# bat_ctl.net
KiCad netlist of a schematic drawn in Altium Designer
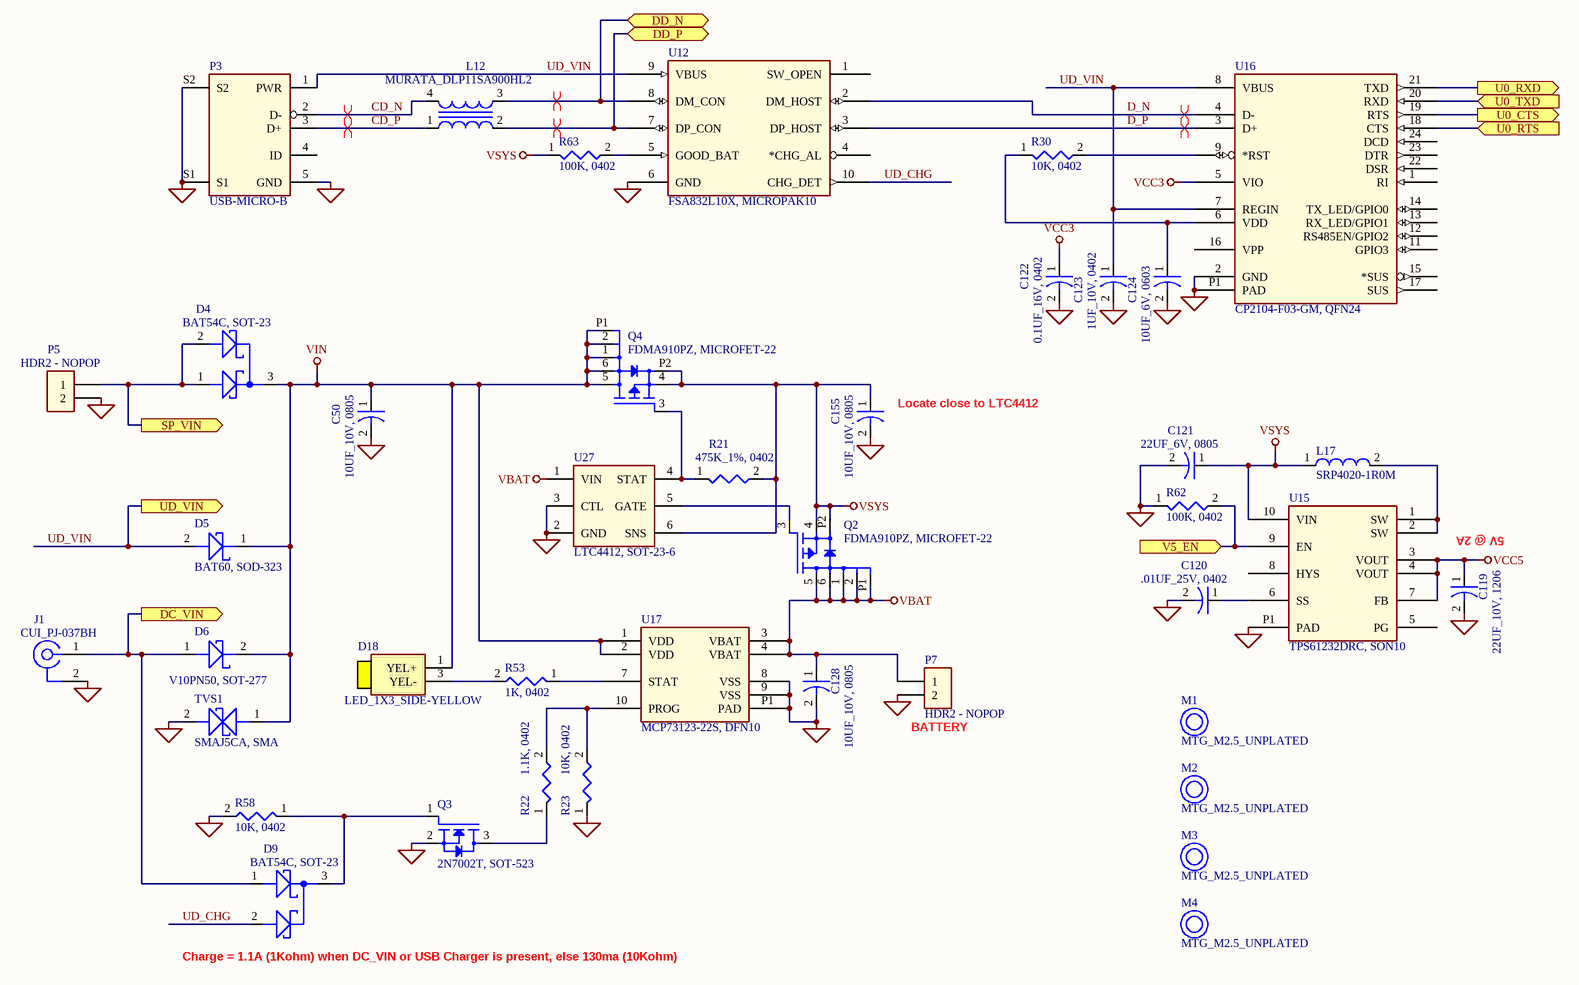
[diagram p0: bat_ctl.SchDoc]

(export (version "E")
  (design (tool "Eeschema 10.0.6"))
  (components
    (comp (ref "C50")
      (value "10UF_10V, 0805")
      (footprint "0805C")
      (description "CAP - 0805 PKG")
      (libsource (lib "COGENT_Library") (part "10UF_10V, 0805"))
    )
    (comp (ref "C119")
      (value "22UF_10V, 1206")
      (footprint "1206C")
      (description "CAP - 1206 PKG")
      (libsource (lib "COGENT_Library") (part "22UF_10V, 1206"))
    )
    (comp (ref "C120")
      (value ".01UF_25V, 0402")
      (footprint "0402C")
      (description "CAP - 0402 PKG")
      (libsource (lib "COGENT_Library") (part ".01UF_25V, 0402"))
    )
    (comp (ref "C121")
      (value "22UF_6V, 0805")
      (footprint "0805C")
      (description "CAP - 0805 PKG")
      (libsource (lib "COGENT_Library") (part "22UF_6V, 0805"))
    )
    (comp (ref "C122")
      (value "0.1UF_16V, 0402")
      (footprint "0402C")
      (description "CAP - 0402 PKG")
      (libsource (lib "COGENT_Library") (part "0.1UF_16V, 0402"))
    )
    (comp (ref "C123")
      (value "1UF_10V, 0402")
      (footprint "0402C")
      (description "CAP - 0402 PKG")
      (libsource (lib "COGENT_Library") (part "1UF_10V, 0402"))
    )
    (comp (ref "C124")
      (value "10UF_6V, 0603")
      (footprint "0603C")
      (description "CAP - 0603 PKG")
      (libsource (lib "COGENT_Library") (part "10UF_6V, 0603"))
    )
    (comp (ref "C128")
      (value "10UF_10V, 0805")
      (footprint "0805C")
      (description "CAP - 0805 PKG")
      (libsource (lib "COGENT_Library") (part "10UF_10V, 0805"))
    )
    (comp (ref "C155")
      (value "10UF_10V, 0805")
      (footprint "0805C")
      (description "CAP - 0805 PKG")
      (libsource (lib "COGENT_Library") (part "10UF_10V, 0805"))
    )
    (comp (ref "D4")
      (value "BAT54C, SOT-23")
      (footprint "SOT-23")
      (description "DIODE - DUAL SCHOTTKY, COMMON CATHODE, 30V, 200MA")
      (libsource (lib "COGENT_Library") (part "BAT54C, SOT-23"))
    )
    (comp (ref "D5")
      (value "BAT60, SOD-323")
      (footprint "SOD-323")
      (description "DIODE - POWER, SCHOTTKY, 10V, 3A")
      (libsource (lib "COGENT_Library") (part "BAT60, SOD-323"))
    )
    (comp (ref "D6")
      (value "V10PN50, SOT-277")
      (footprint "SOT-277")
      (description "DIODE - SCHOTTKY, 50V, 10A")
      (libsource (lib "COGENT_Library") (part "V10PN50, SOT-277"))
    )
    (comp (ref "D9")
      (value "BAT54C, SOT-23")
      (footprint "SOT-23")
      (description "DIODE - DUAL SCHOTTKY, COMMON CATHODE, 30V, 200MA")
      (libsource (lib "COGENT_Library") (part "BAT54C, SOT-23"))
    )
    (comp (ref "D18")
      (value "LED_1X3_SIDE-YELLOW")
      (footprint "LED_1X3_SIDE-YELLOW")
      (description "LED - SIDEVIEW, SMT, YELLOW")
      (libsource (lib "COGENT_Library") (part "LED_1X3_SIDE-YELLOW"))
    )
    (comp (ref "J1")
      (value "CUI_PJ-037BH")
      (footprint "CUI_PJ-037B")
      (description "CONN - DC JACK, 2.5mm CENTER PLUS, 5 AMP")
      (libsource (lib "COGENT_Library") (part "CUI_PJ-037BH"))
    )
    (comp (ref "L12")
      (value "MURATA_DLP11SA900HL2")
      (footprint "PANASONIC_EXC24C")
      (description "FERRITE - COMMON MODE FILTER, USB2/HDMI/GIGe, FILM")
      (libsource (lib "COGENT_Library") (part "MURATA_DLP11SA900HL2"))
    )
    (comp (ref "L17")
      (value "SRP4020-1R0M")
      (footprint "SRP4020")
      (description "INDUCTOR - 1.0UH, 5/6A, 4MM x 4MM x 2MM, 22mohm")
      (libsource (lib "COGENT_Library") (part "SRP4020-1R0M"))
    )
    (comp (ref "M1")
      (value "MTG_M2.5_UNPLATED")
      (footprint "MTG_M2.5_UNPLATED")
      (description "MTG HOLE - 2.75mm HOLE 2-56 OR M2.5")
      (libsource (lib "COGENT_Library") (part "MTG_M2.5_UNPLATED"))
    )
    (comp (ref "M2")
      (value "MTG_M2.5_UNPLATED")
      (footprint "MTG_M2.5_UNPLATED")
      (description "MTG HOLE - 2.75mm HOLE 2-56 OR M2.5")
      (libsource (lib "COGENT_Library") (part "MTG_M2.5_UNPLATED"))
    )
    (comp (ref "M3")
      (value "MTG_M2.5_UNPLATED")
      (footprint "MTG_M2.5_UNPLATED")
      (description "MTG HOLE - 2.75mm HOLE 2-56 OR M2.5")
      (libsource (lib "COGENT_Library") (part "MTG_M2.5_UNPLATED"))
    )
    (comp (ref "M4")
      (value "MTG_M2.5_UNPLATED")
      (footprint "MTG_M2.5_UNPLATED")
      (description "MTG HOLE - 2.75mm HOLE 2-56 OR M2.5")
      (libsource (lib "COGENT_Library") (part "MTG_M2.5_UNPLATED"))
    )
    (comp (ref "P3")
      (value "USB-MICRO-B")
      (footprint "USB-MICRO-B")
      (description "CONN - USB TYPE B MICRO")
      (libsource (lib "COGENT_Library") (part "USB-MICRO-B"))
    )
    (comp (ref "P5")
      (value "HDR2 - NOPOP")
      (footprint "HDR2X1-NOPOP")
      (description "HEADER - 2-PIN, HOLES ONLY FOR WIRE")
      (libsource (lib "") (part "HDR2 - NOPOP_1"))
    )
    (comp (ref "P7")
      (value "HDR2 - NOPOP")
      (footprint "HDR2X1-NOPOP")
      (description "HEADER - 2-PIN, HOLES ONLY FOR WIRE")
      (libsource (lib "COGENT_Library") (part "HDR2 - NOPOP"))
    )
    (comp (ref "Q2")
      (value "FDMA910PZ, MICROFET-22")
      (footprint "MICROFET-22")
      (description "P-FET - 20V, 7.2A @ 1.8Vgs, 34mohm")
      (libsource (lib "COGENT_Library") (part "FDMA910PZ, MICROFET-22"))
    )
    (comp (ref "Q3")
      (value "2N7002T, SOT-523")
      (footprint "SOT-523")
      (description "N-FET - 60V, 500ma @ 10V, Vgs(th) 2V")
      (libsource (lib "COGENT_Library") (part "2N7002T, SOT-523"))
    )
    (comp (ref "Q4")
      (value "FDMA910PZ, MICROFET-22")
      (footprint "MICROFET-22")
      (description "P-FET - 20V, 7.2A @ 1.8Vgs, 34mohm")
      (libsource (lib "COGENT_Library") (part "FDMA910PZ, MICROFET-22"))
    )
    (comp (ref "R21")
      (value "475K_1%, 0402")
      (footprint "0402R")
      (description "RES - 0402 PKG")
      (libsource (lib "COGENT_Library") (part "475K_1%, 0402"))
    )
    (comp (ref "R22")
      (value "1.1K, 0402")
      (footprint "0402R")
      (description "RES - 0402 PKG")
      (libsource (lib "COGENT_Library") (part "1.1K, 0402"))
    )
    (comp (ref "R23")
      (value "10K, 0402")
      (footprint "0402R")
      (description "RES - 0402 PKG")
      (libsource (lib "COGENT_Library") (part "10K, 0402"))
    )
    (comp (ref "R30")
      (value "10K, 0402")
      (footprint "0402R")
      (description "RES - 0402 PKG")
      (libsource (lib "COGENT_Library") (part "10K, 0402"))
    )
    (comp (ref "R53")
      (value "1K, 0402")
      (footprint "0402R")
      (description "RES - 0402 PKG")
      (libsource (lib "COGENT_Library") (part "1K, 0402"))
    )
    (comp (ref "R58")
      (value "10K, 0402")
      (footprint "0402R")
      (description "RES - 0402 PKG")
      (libsource (lib "COGENT_Library") (part "10K, 0402"))
    )
    (comp (ref "R62")
      (value "100K, 0402")
      (footprint "0402R")
      (description "RES - 0402 PKG")
      (libsource (lib "COGENT_Library") (part "100K, 0402"))
    )
    (comp (ref "R63")
      (value "100K, 0402")
      (footprint "0402R")
      (description "RES - 0402 PKG")
      (libsource (lib "COGENT_Library") (part "100K, 0402"))
    )
    (comp (ref "TVS1")
      (value "SMAJ5CA, SMA")
      (footprint "SMA")
      (description "DIODE - TVS, 6.4V MIN., 7.25V MAX.")
      (libsource (lib "COGENT_Library") (part "SMAJ5CA, SMA"))
    )
    (comp (ref "U12")
      (value "FSA832L10X, MICROPAK10")
      (footprint "MICROpack10")
      (description "USB - BATTERY CHARGER DETECTION W/SWITCH")
      (libsource (lib "COGENT_Library") (part "FSA832L10X, MICROPAK10"))
    )
    (comp (ref "U15")
      (value "TPS61232DRC, SON10")
      (footprint "SON10")
      (description "SWITCHER - 500ua Iq, BOOST 5A, 2.3V TO 5.5V IN, 2.5V TO 5.5V OUT")
      (libsource (lib "COGENT_Library") (part "TPS61232DRC, SON10"))
    )
    (comp (ref "U16")
      (value "CP2104-F03-GM, QFN24")
      (footprint "QFN24")
      (description "USB - UART W/4 GPIO")
      (libsource (lib "COGENT_Library") (part "CP2104-F03-GM, QFN24"))
    )
    (comp (ref "U17")
      (value "MCP73123-22S, DFN10")
      (footprint "DFN10")
      (description "IC - BATTERY CHARGER, 1 CELL LiFePO4, 1.1 AMAX")
      (libsource (lib "COGENT_Library") (part "MCP73123-22S, DFN10"))
    )
    (comp (ref "U27")
      (value "LTC4412, SOT-23-6")
      (footprint "SOT-23-6")
      (description "IC - POWER SOURCE SELECTOR")
      (libsource (lib "COGENT_Library") (part "LTC4412, SOT-23-6"))
    )
  )
  (nets
    (net (code "1") (name "/CD_N") (class "Default")
      (node (ref "L12") (pin "4") (pinfunction "4_4") (pintype "passive"))
      (node (ref "P3") (pin "2") (pinfunction "D-_2") (pintype "passive"))
    )
    (net (code "2") (name "/CD_P") (class "Default")
      (node (ref "L12") (pin "1") (pinfunction "1_1") (pintype "passive"))
      (node (ref "P3") (pin "3") (pinfunction "D+_3") (pintype "passive"))
    )
    (net (code "3") (name "/DC_VIN") (class "Default")
      (node (ref "D6") (pin "1") (pinfunction "ANODE_1") (pintype "passive"))
      (node (ref "D9") (pin "1") (pinfunction "1_1") (pintype "passive"))
      (node (ref "J1") (pin "1") (pinfunction "1_1") (pintype "passive"))
    )
    (net (code "4") (name "/DD_N") (class "Default")
      (node (ref "L12") (pin "3") (pinfunction "3_3") (pintype "passive"))
      (node (ref "U12") (pin "8") (pinfunction "DM_CON_8") (pintype "bidirectional"))
    )
    (net (code "5") (name "/DD_P") (class "Default")
      (node (ref "L12") (pin "2") (pinfunction "2_2") (pintype "passive"))
      (node (ref "U12") (pin "7") (pinfunction "DP_CON_7") (pintype "bidirectional"))
    )
    (net (code "6") (name "/D_N") (class "Default")
      (node (ref "U12") (pin "2") (pinfunction "DM_HOST_2") (pintype "bidirectional"))
      (node (ref "U16") (pin "4") (pinfunction "D-_4") (pintype "passive"))
    )
    (net (code "7") (name "/D_P") (class "Default")
      (node (ref "U12") (pin "3") (pinfunction "DP_HOST_3") (pintype "bidirectional"))
      (node (ref "U16") (pin "3") (pinfunction "D+_3") (pintype "passive"))
    )
    (net (code "8") (name "/SP_VIN") (class "Default")
      (node (ref "D4") (pin "1") (pinfunction "1_1") (pintype "passive"))
      (node (ref "D4") (pin "2") (pinfunction "2_2") (pintype "passive"))
      (node (ref "P5") (pin "1") (pinfunction "1_1") (pintype "passive"))
    )
    (net (code "9") (name "/U0_CTS") (class "Default")
      (node (ref "U16") (pin "19") (pinfunction "RTS_19") (pintype "output"))
    )
    (net (code "10") (name "/U0_RTS") (class "Default")
      (node (ref "U16") (pin "18") (pinfunction "CTS_18") (pintype "input"))
    )
    (net (code "11") (name "/U0_RXD") (class "Default")
      (node (ref "U16") (pin "21") (pinfunction "TXD_21") (pintype "output"))
    )
    (net (code "12") (name "/U0_TXD") (class "Default")
      (node (ref "U16") (pin "20") (pinfunction "RXD_20") (pintype "input"))
    )
    (net (code "13") (name "/UD_CHG") (class "Default")
      (node (ref "D9") (pin "2") (pinfunction "2_2") (pintype "passive"))
      (node (ref "U12") (pin "10") (pinfunction "CHG_DET_10") (pintype "output"))
    )
    (net (code "14") (name "/UD_VIN") (class "Default")
      (node (ref "C123") (pin "1") (pinfunction "1_1") (pintype "passive"))
      (node (ref "D5") (pin "2") (pinfunction "ANODE_2") (pintype "passive"))
      (node (ref "P3") (pin "1") (pinfunction "PWR_1") (pintype "passive"))
      (node (ref "U12") (pin "9") (pinfunction "VBUS_9") (pintype "input"))
      (node (ref "U16") (pin "7") (pinfunction "REGIN_7") (pintype "power_in"))
      (node (ref "U16") (pin "8") (pinfunction "VBUS_8") (pintype "passive"))
    )
    (net (code "15") (name "/V5_EN") (class "Default")
      (node (ref "R62") (pin "2") (pinfunction "2_2") (pintype "passive"))
      (node (ref "U15") (pin "9") (pinfunction "EN_9") (pintype "passive"))
    )
    (net (code "16") (name "GND") (class "Default")
      (node (ref "C119") (pin "2") (pinfunction "2_2") (pintype "passive"))
      (node (ref "C120") (pin "2") (pinfunction "2_2") (pintype "passive"))
      (node (ref "C121") (pin "2") (pinfunction "2_2") (pintype "passive"))
      (node (ref "C122") (pin "2") (pinfunction "2_2") (pintype "passive"))
      (node (ref "C123") (pin "2") (pinfunction "2_2") (pintype "passive"))
      (node (ref "C124") (pin "2") (pinfunction "2_2") (pintype "passive"))
      (node (ref "C128") (pin "2") (pinfunction "2_2") (pintype "passive"))
      (node (ref "C155") (pin "2") (pinfunction "2_2") (pintype "passive"))
      (node (ref "C50") (pin "2") (pinfunction "2_2") (pintype "passive"))
      (node (ref "J1") (pin "2") (pinfunction "2_2") (pintype "passive"))
      (node (ref "P3") (pin "5") (pinfunction "GND_5") (pintype "passive"))
      (node (ref "P3") (pin "S1") (pinfunction "S1_S1") (pintype "passive"))
      (node (ref "P3") (pin "S2") (pinfunction "S2_S2") (pintype "passive"))
      (node (ref "P5") (pin "2") (pinfunction "2_2") (pintype "passive"))
      (node (ref "P7") (pin "2") (pinfunction "2_2") (pintype "passive"))
      (node (ref "Q3") (pin "2") (pinfunction "SOURCE_2") (pintype "passive"))
      (node (ref "R23") (pin "1") (pinfunction "1_1") (pintype "passive"))
      (node (ref "R58") (pin "2") (pinfunction "2_2") (pintype "passive"))
      (node (ref "R62") (pin "1") (pinfunction "1_1") (pintype "passive"))
      (node (ref "TVS1") (pin "2") (pinfunction "2_2") (pintype "passive"))
      (node (ref "U12") (pin "6") (pinfunction "GND_6") (pintype "power_in"))
      (node (ref "U15") (pin "P1") (pinfunction "PAD_P1") (pintype "power_in"))
      (node (ref "U16") (pin "2") (pinfunction "GND_2") (pintype "power_in"))
      (node (ref "U16") (pin "P1") (pinfunction "PAD_P1") (pintype "passive"))
      (node (ref "U17") (pin "8") (pinfunction "VSS_8") (pintype "passive"))
      (node (ref "U17") (pin "9") (pinfunction "VSS_9") (pintype "passive"))
      (node (ref "U17") (pin "P1") (pinfunction "PAD_P1") (pintype "passive"))
      (node (ref "U27") (pin "2") (pinfunction "GND_2") (pintype "passive"))
      (node (ref "U27") (pin "3") (pinfunction "CTL_3") (pintype "passive"))
    )
    (net (code "17") (name "Net-(D18-YEL-)") (class "Default")
      (node (ref "D18") (pin "3") (pinfunction "YEL-_3") (pintype "passive"))
      (node (ref "R53") (pin "2") (pinfunction "2_2") (pintype "passive"))
    )
    (net (code "18") (name "Net-(L17-Pad2)") (class "Default")
      (node (ref "L17") (pin "2") (pinfunction "2_2") (pintype "passive"))
      (node (ref "U15") (pin "1") (pinfunction "SW_1") (pintype "open_collector"))
      (node (ref "U15") (pin "2") (pinfunction "SW_2") (pintype "passive"))
    )
    (net (code "19") (name "Net-(Q3-DRAIN)") (class "Default")
      (node (ref "Q3") (pin "3") (pinfunction "DRAIN_3") (pintype "passive"))
      (node (ref "R22") (pin "1") (pinfunction "1_1") (pintype "passive"))
    )
    (net (code "20") (name "Net-(Q3-GATE)") (class "Default")
      (node (ref "D9") (pin "3") (pinfunction "3_3") (pintype "passive"))
      (node (ref "Q3") (pin "1") (pinfunction "GATE_1") (pintype "passive"))
      (node (ref "R58") (pin "1") (pinfunction "1_1") (pintype "passive"))
    )
    (net (code "21") (name "Net-(U12-GOOD_BAT)") (class "Default")
      (node (ref "R63") (pin "2") (pinfunction "2_2") (pintype "passive"))
      (node (ref "U12") (pin "5") (pinfunction "GOOD_BAT_5") (pintype "input"))
    )
    (net (code "22") (name "Net-(U15-SS)") (class "Default")
      (node (ref "C120") (pin "1") (pinfunction "1_1") (pintype "passive"))
      (node (ref "U15") (pin "6") (pinfunction "SS_6") (pintype "passive"))
    )
    (net (code "23") (name "Net-(U16-*RST)") (class "Default")
      (node (ref "R30") (pin "2") (pinfunction "2_2") (pintype "passive"))
      (node (ref "U16") (pin "9") (pinfunction "*RST_9") (pintype "bidirectional"))
    )
    (net (code "24") (name "Net-(U16-VDD)") (class "Default")
      (node (ref "C124") (pin "1") (pinfunction "1_1") (pintype "passive"))
      (node (ref "R30") (pin "1") (pinfunction "1_1") (pintype "passive"))
      (node (ref "U16") (pin "6") (pinfunction "VDD_6") (pintype "power_in"))
    )
    (net (code "25") (name "Net-(U17-PROG)") (class "Default")
      (node (ref "R22") (pin "2") (pinfunction "2_2") (pintype "passive"))
      (node (ref "R23") (pin "2") (pinfunction "2_2") (pintype "passive"))
      (node (ref "U17") (pin "10") (pinfunction "PROG_10") (pintype "passive"))
    )
    (net (code "26") (name "Net-(U17-STAT)") (class "Default")
      (node (ref "R53") (pin "1") (pinfunction "1_1") (pintype "passive"))
      (node (ref "U17") (pin "7") (pinfunction "STAT_7") (pintype "open_collector"))
    )
    (net (code "27") (name "Net-(U27-GATE)") (class "Default")
      (node (ref "Q2") (pin "3") (pinfunction "3_3") (pintype "passive"))
      (node (ref "U27") (pin "5") (pinfunction "GATE_5") (pintype "passive"))
    )
    (net (code "28") (name "Net-(U27-STAT)") (class "Default")
      (node (ref "Q4") (pin "3") (pinfunction "3_3") (pintype "passive"))
      (node (ref "R21") (pin "1") (pinfunction "1_1") (pintype "passive"))
      (node (ref "U27") (pin "4") (pinfunction "STAT_4") (pintype "passive"))
    )
    (net (code "29") (name "VBAT") (class "Default")
      (node (ref "C128") (pin "1") (pinfunction "1_1") (pintype "passive"))
      (node (ref "P7") (pin "1") (pinfunction "1_1") (pintype "passive"))
      (node (ref "Q2") (pin "1") (pinfunction "1_1") (pintype "passive"))
      (node (ref "Q2") (pin "2") (pinfunction "2_2") (pintype "passive"))
      (node (ref "Q2") (pin "5") (pinfunction "D1_5") (pintype "passive"))
      (node (ref "Q2") (pin "6") (pinfunction "D2_6") (pintype "passive"))
      (node (ref "Q2") (pin "P1") (pinfunction "D5_P1") (pintype "passive"))
      (node (ref "U17") (pin "3") (pinfunction "VBAT_3") (pintype "passive"))
      (node (ref "U17") (pin "4") (pinfunction "VBAT_4") (pintype "passive"))
      (node (ref "U27") (pin "1") (pinfunction "VIN_1") (pintype "passive"))
    )
    (net (code "30") (name "VCC3") (class "Default")
      (node (ref "C122") (pin "1") (pinfunction "1_1") (pintype "passive"))
      (node (ref "U16") (pin "5") (pinfunction "VIO_5") (pintype "power_in"))
    )
    (net (code "31") (name "VCC5") (class "Default")
      (node (ref "C119") (pin "1") (pinfunction "1_1") (pintype "passive"))
      (node (ref "U15") (pin "3") (pinfunction "VOUT_3") (pintype "passive"))
      (node (ref "U15") (pin "4") (pinfunction "VOUT_4") (pintype "passive"))
      (node (ref "U15") (pin "7") (pinfunction "FB_7") (pintype "power_in"))
    )
    (net (code "32") (name "VIN") (class "Default")
      (node (ref "C50") (pin "1") (pinfunction "1_1") (pintype "passive"))
      (node (ref "D18") (pin "1") (pinfunction "YEL+_1") (pintype "passive"))
      (node (ref "D4") (pin "3") (pinfunction "3_3") (pintype "passive"))
      (node (ref "D5") (pin "1") (pinfunction "CATHODE_1") (pintype "passive"))
      (node (ref "D6") (pin "2") (pinfunction "CATHODE_2") (pintype "passive"))
      (node (ref "Q4") (pin "1") (pinfunction "1_1") (pintype "passive"))
      (node (ref "Q4") (pin "2") (pinfunction "2_2") (pintype "passive"))
      (node (ref "Q4") (pin "5") (pinfunction "D1_5") (pintype "passive"))
      (node (ref "Q4") (pin "6") (pinfunction "D2_6") (pintype "passive"))
      (node (ref "Q4") (pin "P1") (pinfunction "D5_P1") (pintype "passive"))
      (node (ref "TVS1") (pin "1") (pinfunction "1_1") (pintype "passive"))
      (node (ref "U17") (pin "1") (pinfunction "VDD_1") (pintype "passive"))
      (node (ref "U17") (pin "2") (pinfunction "VDD_2") (pintype "passive"))
    )
    (net (code "33") (name "VSYS") (class "Default")
      (node (ref "C121") (pin "1") (pinfunction "1_1") (pintype "passive"))
      (node (ref "C155") (pin "1") (pinfunction "1_1") (pintype "passive"))
      (node (ref "L17") (pin "1") (pinfunction "1_1") (pintype "passive"))
      (node (ref "Q2") (pin "4") (pinfunction "4_4") (pintype "passive"))
      (node (ref "Q2") (pin "P2") (pinfunction "P2_P2") (pintype "passive"))
      (node (ref "Q4") (pin "4") (pinfunction "4_4") (pintype "passive"))
      (node (ref "Q4") (pin "P2") (pinfunction "P2_P2") (pintype "passive"))
      (node (ref "R21") (pin "2") (pinfunction "2_2") (pintype "passive"))
      (node (ref "R63") (pin "1") (pinfunction "1_1") (pintype "passive"))
      (node (ref "U15") (pin "10") (pinfunction "VIN_10") (pintype "passive"))
      (node (ref "U27") (pin "6") (pinfunction "SNS_6") (pintype "passive"))
    )
    (net (code "34") (name "unconnected-(P3-ID-Pad4)") (class "Default")
      (node (ref "P3") (pin "4") (pinfunction "ID_4") (pintype "passive"))
    )
    (net (code "35") (name "unconnected-(U12-*CHG_AL-Pad4)") (class "Default")
      (node (ref "U12") (pin "4") (pinfunction "*CHG_AL_4") (pintype "open_collector"))
    )
    (net (code "36") (name "unconnected-(U12-SW_OPEN-Pad1)") (class "Default")
      (node (ref "U12") (pin "1") (pinfunction "SW_OPEN_1") (pintype "open_collector"))
    )
    (net (code "37") (name "unconnected-(U15-HYS-Pad8)") (class "Default")
      (node (ref "U15") (pin "8") (pinfunction "HYS_8") (pintype "passive"))
    )
    (net (code "38") (name "unconnected-(U15-PG-Pad5)") (class "Default")
      (node (ref "U15") (pin "5") (pinfunction "PG_5") (pintype "passive"))
    )
    (net (code "39") (name "unconnected-(U16-*SUS-Pad15)") (class "Default")
      (node (ref "U16") (pin "15") (pinfunction "*SUS_15") (pintype "output"))
    )
    (net (code "40") (name "unconnected-(U16-DCD-Pad24)") (class "Default")
      (node (ref "U16") (pin "24") (pinfunction "DCD_24") (pintype "input"))
    )
    (net (code "41") (name "unconnected-(U16-DSR-Pad22)") (class "Default")
      (node (ref "U16") (pin "22") (pinfunction "DSR_22") (pintype "input"))
    )
    (net (code "42") (name "unconnected-(U16-DTR-Pad23)") (class "Default")
      (node (ref "U16") (pin "23") (pinfunction "DTR_23") (pintype "output"))
    )
    (net (code "43") (name "unconnected-(U16-GPIO3-Pad11)") (class "Default")
      (node (ref "U16") (pin "11") (pinfunction "GPIO3_11") (pintype "bidirectional"))
    )
    (net (code "44") (name "unconnected-(U16-RI-Pad1)") (class "Default")
      (node (ref "U16") (pin "1") (pinfunction "RI_1") (pintype "input"))
    )
    (net (code "45") (name "unconnected-(U16-RS485EN{slash}GPIO2-Pad12)") (class "Default")
      (node (ref "U16") (pin "12") (pinfunction "RS485EN/GPIO2_12") (pintype "bidirectional"))
    )
    (net (code "46") (name "unconnected-(U16-RX_LED{slash}GPIO1-Pad13)") (class "Default")
      (node (ref "U16") (pin "13") (pinfunction "RX_LED/GPIO1_13") (pintype "bidirectional"))
    )
    (net (code "47") (name "unconnected-(U16-SUS-Pad17)") (class "Default")
      (node (ref "U16") (pin "17") (pinfunction "SUS_17") (pintype "output"))
    )
    (net (code "48") (name "unconnected-(U16-TX_LED{slash}GPIO0-Pad14)") (class "Default")
      (node (ref "U16") (pin "14") (pinfunction "TX_LED/GPIO0_14") (pintype "bidirectional"))
    )
    (net (code "49") (name "unconnected-(U16-VPP-Pad16)") (class "Default")
      (node (ref "U16") (pin "16") (pinfunction "VPP_16") (pintype "power_in"))
    )
  )
)
